# smd.net
KiCad netlist of a schematic drawn in EAGLE
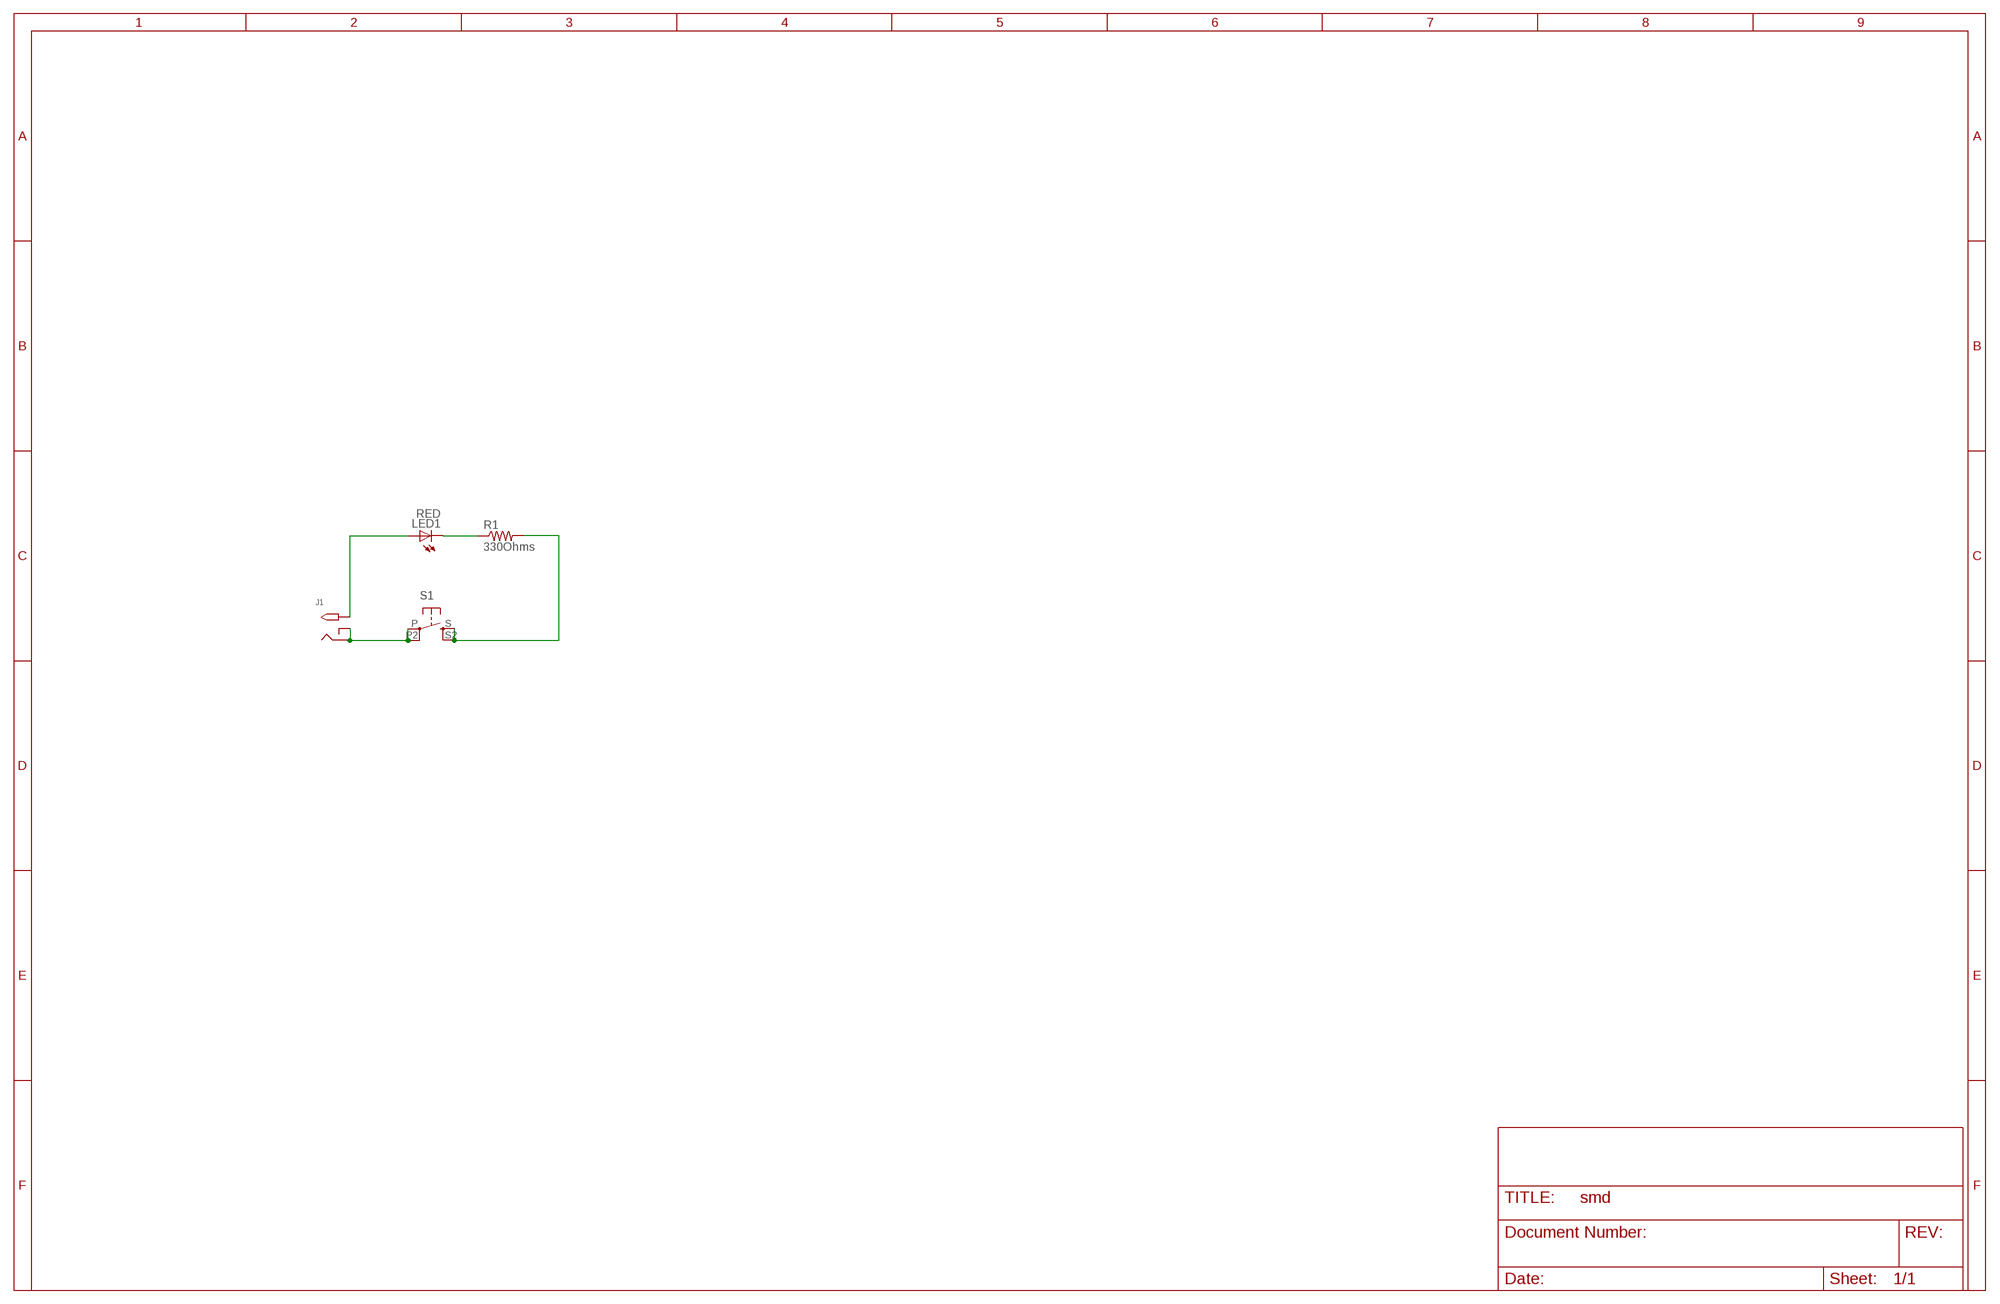
[diagram p0: schematic, sheet 1]

(export (version "E")
  (design (tool "Eeschema 10.0.6"))
  (components
    (comp (ref "J1")
      (value "2.1MMJACKTHM")
      (footprint "eagle-import:PJ-102A")
      (fields (field (name "CREATOR") "Swanson") (field (name "REVIEWER") "Swanson"))
      (libsource (lib "eagle-import") (part "2.1MMJACKTHM"))
    )
    (comp (ref "LED1")
      (value "RED")
      (footprint "eagle-import:LED5MM")
      (fields (field (name "CREATOR") "Swanson") (field (name "REVIEWER") "Swanson"))
      (libsource (lib "eagle-import") (part "LED5MM"))
    )
    (comp (ref "R1")
      (value "330Ohms")
      (footprint "eagle-import:RESAD1160W55L680D260_HS")
      (fields (field (name "CREATOR") "Swanson") (field (name "REVIEWER") "Swanson"))
      (libsource (lib "eagle-import") (part "RESISTORTH-1/4W-CARBON"))
    )
    (comp (ref "S1")
      (value "BUTTON-TACTILE-SMD")
      (footprint "eagle-import:BUTTON-TACTILE-SMD")
      (fields (field (name "CREATOR") "PBROWN") (field (name "REVIEWER") "Swanson"))
      (libsource (lib "eagle-import") (part "BUTTON-TACTILE-SMD"))
    )
  )
  (nets
    (net (code "1") (name "Net-(J1-PadTIP)") (class "Default")
      (node (ref "J1") (pin "TIP") (pinfunction "TIP_TIP") (pintype "bidirectional"))
      (node (ref "LED1") (pin "A") (pinfunction "A_A") (pintype "passive"))
    )
    (net (code "2") (name "Net-(LED1-C)") (class "Default")
      (node (ref "LED1") (pin "K") (pinfunction "C_K") (pintype "passive"))
      (node (ref "R1") (pin "1") (pinfunction "1_1") (pintype "passive"))
    )
    (net (code "3") (name "Net-(S1-P1)") (class "Default")
      (node (ref "J1") (pin "RING") (pinfunction "RING_RING") (pintype "bidirectional"))
      (node (ref "J1") (pin "RING_SW") (pinfunction "RING_SW_RING_SW") (pintype "bidirectional"))
      (node (ref "S1") (pin "P") (pinfunction "P_P") (pintype "passive"))
      (node (ref "S1") (pin "P2") (pinfunction "P1_P2") (pintype "passive"))
    )
    (net (code "4") (name "Net-(S1-S1)") (class "Default")
      (node (ref "R1") (pin "2") (pinfunction "2_2") (pintype "passive"))
      (node (ref "S1") (pin "S") (pinfunction "S_S") (pintype "passive"))
      (node (ref "S1") (pin "S2") (pinfunction "S1_S2") (pintype "passive"))
    )
  )
)
